# Mainsnode.net
KiCad netlist of a schematic drawn in EAGLE
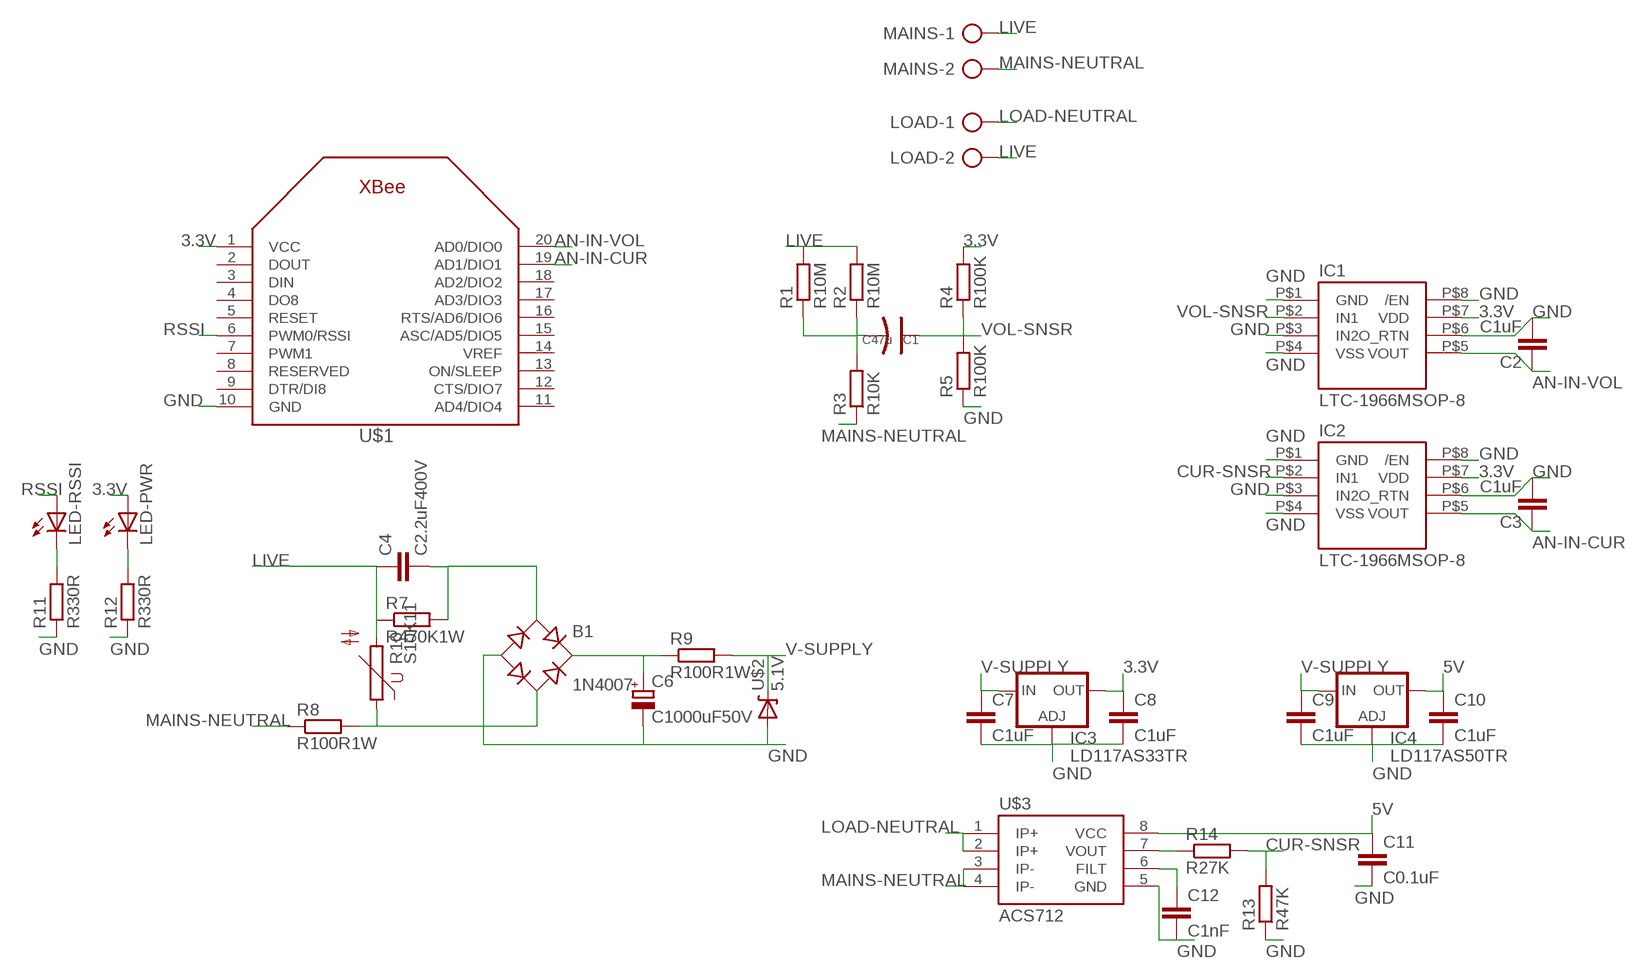
[diagram p0: schematic, sheet 1]

(export (version "E")
  (design (tool "Eeschema 10.0.6"))
  (components
    (comp (ref "B1")
      (value "1N4007")
      (footprint "eagle-import:RB1A")
      (libsource (lib "eagle-import") (part "RB1A"))
    )
    (comp (ref "C1")
      (value "C47u")
      (footprint "eagle-import:AVX-C")
      (libsource (lib "eagle-import") (part "C-POLAR-C"))
    )
    (comp (ref "C2")
      (value "C1uF")
      (footprint "eagle-import:C0805")
      (libsource (lib "eagle-import") (part "C-EUC0805"))
    )
    (comp (ref "C3")
      (value "C1uF")
      (footprint "eagle-import:C0805")
      (libsource (lib "eagle-import") (part "C-EUC0805"))
    )
    (comp (ref "C4")
      (value "C2.2uF400V")
      (footprint "eagle-import:C150-064X183")
      (libsource (lib "eagle-import") (part "C-EU150-064X183"))
    )
    (comp (ref "C6")
      (value "C1000uF50V")
      (footprint "eagle-import:E2-5")
      (libsource (lib "eagle-import") (part "CPOL-EUE2-5"))
    )
    (comp (ref "C7")
      (value "C1uF")
      (footprint "eagle-import:C0805")
      (libsource (lib "eagle-import") (part "C-EUC0805"))
    )
    (comp (ref "C8")
      (value "C1uF")
      (footprint "eagle-import:C0805")
      (libsource (lib "eagle-import") (part "C-EUC0805"))
    )
    (comp (ref "C9")
      (value "C1uF")
      (footprint "eagle-import:C0805")
      (libsource (lib "eagle-import") (part "C-EUC0805"))
    )
    (comp (ref "C10")
      (value "C1uF")
      (footprint "eagle-import:C0805")
      (libsource (lib "eagle-import") (part "C-EUC0805"))
    )
    (comp (ref "C11")
      (value "C0.1uF")
      (footprint "eagle-import:C0805")
      (libsource (lib "eagle-import") (part "C-EUC0805"))
    )
    (comp (ref "C12")
      (value "C1nF")
      (footprint "eagle-import:C0805")
      (libsource (lib "eagle-import") (part "C-EUC0805"))
    )
    (comp (ref "IC1")
      (value "LTC-1966MSOP-8")
      (footprint "eagle-import:MSOP-8")
      (libsource (lib "eagle-import") (part "LTC-1966MSOP-8"))
    )
    (comp (ref "IC2")
      (value "LTC-1966MSOP-8")
      (footprint "eagle-import:MSOP-8")
      (libsource (lib "eagle-import") (part "LTC-1966MSOP-8"))
    )
    (comp (ref "IC3")
      (value "LD117AS33TR")
      (footprint "eagle-import:SOT223")
      (libsource (lib "eagle-import") (part "LD117A?S33TR"))
    )
    (comp (ref "IC4")
      (value "LD117AS50TR")
      (footprint "eagle-import:SOT223")
      (libsource (lib "eagle-import") (part "LD117A?S50TR"))
    )
    (comp (ref "LED-PWR")
      (value "LED0603")
      (footprint "eagle-import:LED-0603")
      (libsource (lib "eagle-import") (part "LED0603"))
    )
    (comp (ref "LED-RSSI")
      (value "LED0603")
      (footprint "eagle-import:LED-0603")
      (libsource (lib "eagle-import") (part "LED0603"))
    )
    (comp (ref "LOAD")
      (value "AK300/2")
      (footprint "eagle-import:AK300_2")
      (libsource (lib "eagle-import") (part "AK300/2"))
    )
    (comp (ref "MAINS")
      (value "AK300/2")
      (footprint "eagle-import:AK300_2")
      (libsource (lib "eagle-import") (part "AK300/2"))
    )
    (comp (ref "R1")
      (value "R10M")
      (footprint "eagle-import:0309V")
      (libsource (lib "eagle-import") (part "R-EU_0309/V"))
    )
    (comp (ref "R2")
      (value "R10M")
      (footprint "eagle-import:R0603")
      (libsource (lib "eagle-import") (part "R-EU_R0603"))
    )
    (comp (ref "R3")
      (value "R10K")
      (footprint "eagle-import:R0603")
      (libsource (lib "eagle-import") (part "R-EU_R0603"))
    )
    (comp (ref "R4")
      (value "R100K")
      (footprint "eagle-import:R0603")
      (libsource (lib "eagle-import") (part "R-EU_R0603"))
    )
    (comp (ref "R5")
      (value "R100K")
      (footprint "eagle-import:R0603")
      (libsource (lib "eagle-import") (part "R-EU_R0603"))
    )
    (comp (ref "R7")
      (value "R470K1W")
      (footprint "eagle-import:0309V")
      (libsource (lib "eagle-import") (part "R-EU_0309/V"))
    )
    (comp (ref "R8")
      (value "R100R1W")
      (footprint "eagle-import:0309V")
      (libsource (lib "eagle-import") (part "R-EU_0309/V"))
    )
    (comp (ref "R9")
      (value "R100R1W")
      (footprint "eagle-import:0309V")
      (libsource (lib "eagle-import") (part "R-EU_0309/V"))
    )
    (comp (ref "R10")
      (value "S10K11")
      (footprint "eagle-import:S10K11")
      (libsource (lib "eagle-import") (part "S10K11"))
    )
    (comp (ref "R11")
      (value "R330R")
      (footprint "eagle-import:R0603")
      (libsource (lib "eagle-import") (part "R-EU_R0603"))
    )
    (comp (ref "R12")
      (value "R330R")
      (footprint "eagle-import:R0603")
      (libsource (lib "eagle-import") (part "R-EU_R0603"))
    )
    (comp (ref "R13")
      (value "R47K")
      (footprint "eagle-import:R0603")
      (libsource (lib "eagle-import") (part "R-EU_R0603"))
    )
    (comp (ref "R14")
      (value "R27K")
      (footprint "eagle-import:R0603")
      (libsource (lib "eagle-import") (part "R-EU_R0603"))
    )
    (comp (ref "U$1")
      (value "XBEE")
      (footprint "eagle-import:XBEE")
      (libsource (lib "eagle-import") (part "XBEE"))
    )
    (comp (ref "U$2")
      (value "5.1V")
      (footprint "eagle-import:DIODE-ZENER")
      (libsource (lib "eagle-import") (part "DIODE-ZENERPTH"))
    )
    (comp (ref "U$3")
      (value "ACS712")
      (footprint "eagle-import:SO08")
      (libsource (lib "eagle-import") (part "ACS712"))
    )
  )
  (nets
    (net (code "1") (name "/3.3V") (class "Default")
      (node (ref "C8") (pin "1") (pinfunction "1_1") (pintype "passive"))
      (node (ref "IC1") (pin "P$7") (pinfunction "VDD_P$7") (pintype "bidirectional"))
      (node (ref "IC2") (pin "P$7") (pinfunction "VDD_P$7") (pintype "bidirectional"))
      (node (ref "IC3") (pin "4") (pinfunction "OUT_4") (pintype "passive"))
      (node (ref "LED-PWR") (pin "A") (pinfunction "A_A") (pintype "passive"))
      (node (ref "R4") (pin "2") (pinfunction "2_2") (pintype "passive"))
      (node (ref "U$1") (pin "1") (pinfunction "VCC_1") (pintype "power_in"))
    )
    (net (code "2") (name "/5V") (class "Default")
      (node (ref "C10") (pin "1") (pinfunction "1_1") (pintype "passive"))
      (node (ref "C11") (pin "1") (pinfunction "1_1") (pintype "passive"))
      (node (ref "IC4") (pin "4") (pinfunction "OUT_4") (pintype "passive"))
      (node (ref "U$3") (pin "8") (pinfunction "VCC_8") (pintype "bidirectional"))
    )
    (net (code "3") (name "/AN-IN-CUR") (class "Default")
      (node (ref "C3") (pin "1") (pinfunction "1_1") (pintype "passive"))
      (node (ref "IC2") (pin "P$5") (pinfunction "VOUT_P$5") (pintype "bidirectional"))
      (node (ref "U$1") (pin "19") (pinfunction "AD1/DIO1_19") (pintype "bidirectional"))
    )
    (net (code "4") (name "/AN-IN-VOL") (class "Default")
      (node (ref "C2") (pin "1") (pinfunction "1_1") (pintype "passive"))
      (node (ref "IC1") (pin "P$5") (pinfunction "VOUT_P$5") (pintype "bidirectional"))
      (node (ref "U$1") (pin "20") (pinfunction "AD0/DIO0_20") (pintype "bidirectional"))
    )
    (net (code "5") (name "/CUR-SNSR") (class "Default")
      (node (ref "IC2") (pin "P$2") (pinfunction "IN1_P$2") (pintype "bidirectional"))
      (node (ref "R13") (pin "2") (pinfunction "2_2") (pintype "passive"))
      (node (ref "R14") (pin "2") (pinfunction "2_2") (pintype "passive"))
    )
    (net (code "6") (name "/GND") (class "Default")
      (node (ref "B1") (pin "-") (pinfunction "-_-") (pintype "passive"))
      (node (ref "C10") (pin "2") (pinfunction "2_2") (pintype "passive"))
      (node (ref "C11") (pin "2") (pinfunction "2_2") (pintype "passive"))
      (node (ref "C12") (pin "2") (pinfunction "2_2") (pintype "passive"))
      (node (ref "C2") (pin "2") (pinfunction "2_2") (pintype "passive"))
      (node (ref "C3") (pin "2") (pinfunction "2_2") (pintype "passive"))
      (node (ref "C6") (pin "-") (pinfunction "-_-") (pintype "passive"))
      (node (ref "C7") (pin "2") (pinfunction "2_2") (pintype "passive"))
      (node (ref "C8") (pin "2") (pinfunction "2_2") (pintype "passive"))
      (node (ref "C9") (pin "2") (pinfunction "2_2") (pintype "passive"))
      (node (ref "IC1") (pin "P$1") (pinfunction "GND_P$1") (pintype "bidirectional"))
      (node (ref "IC1") (pin "P$3") (pinfunction "IN2_P$3") (pintype "bidirectional"))
      (node (ref "IC1") (pin "P$4") (pinfunction "VSS_P$4") (pintype "bidirectional"))
      (node (ref "IC1") (pin "P$6") (pinfunction "O_RTN_P$6") (pintype "bidirectional"))
      (node (ref "IC1") (pin "P$8") (pinfunction "/EN_P$8") (pintype "bidirectional"))
      (node (ref "IC2") (pin "P$1") (pinfunction "GND_P$1") (pintype "bidirectional"))
      (node (ref "IC2") (pin "P$3") (pinfunction "IN2_P$3") (pintype "bidirectional"))
      (node (ref "IC2") (pin "P$4") (pinfunction "VSS_P$4") (pintype "bidirectional"))
      (node (ref "IC2") (pin "P$6") (pinfunction "O_RTN_P$6") (pintype "bidirectional"))
      (node (ref "IC2") (pin "P$8") (pinfunction "/EN_P$8") (pintype "bidirectional"))
      (node (ref "IC3") (pin "1") (pinfunction "ADJ_1") (pintype "input"))
      (node (ref "IC4") (pin "1") (pinfunction "ADJ_1") (pintype "input"))
      (node (ref "R11") (pin "1") (pinfunction "1_1") (pintype "passive"))
      (node (ref "R12") (pin "1") (pinfunction "1_1") (pintype "passive"))
      (node (ref "R13") (pin "1") (pinfunction "1_1") (pintype "passive"))
      (node (ref "R5") (pin "1") (pinfunction "1_1") (pintype "passive"))
      (node (ref "U$1") (pin "10") (pinfunction "GND_10") (pintype "power_in"))
      (node (ref "U$2") (pin "P$2") (pinfunction "A_P$2") (pintype "passive"))
      (node (ref "U$3") (pin "5") (pinfunction "GND_5") (pintype "bidirectional"))
    )
    (net (code "7") (name "/LIVE") (class "Default")
      (node (ref "C4") (pin "1") (pinfunction "1_1") (pintype "passive"))
      (node (ref "LOAD") (pin "2") (pinfunction "KL_2") (pintype "passive"))
      (node (ref "MAINS") (pin "1") (pinfunction "KL_1") (pintype "passive"))
      (node (ref "R1") (pin "2") (pinfunction "2_2") (pintype "passive"))
      (node (ref "R10") (pin "2") (pinfunction "2_2") (pintype "passive"))
      (node (ref "R2") (pin "2") (pinfunction "2_2") (pintype "passive"))
      (node (ref "R7") (pin "1") (pinfunction "1_1") (pintype "passive"))
    )
    (net (code "8") (name "/LOAD-NEUTRAL") (class "Default")
      (node (ref "LOAD") (pin "1") (pinfunction "KL_1") (pintype "passive"))
      (node (ref "U$3") (pin "1") (pinfunction "IP+_1") (pintype "bidirectional"))
      (node (ref "U$3") (pin "2") (pinfunction "IP+_2") (pintype "bidirectional"))
    )
    (net (code "9") (name "/MAINS-NEUTRAL") (class "Default")
      (node (ref "MAINS") (pin "2") (pinfunction "KL_2") (pintype "passive"))
      (node (ref "R3") (pin "1") (pinfunction "1_1") (pintype "passive"))
      (node (ref "R8") (pin "1") (pinfunction "1_1") (pintype "passive"))
      (node (ref "U$3") (pin "3") (pinfunction "IP-_3") (pintype "bidirectional"))
      (node (ref "U$3") (pin "4") (pinfunction "IP-_4") (pintype "bidirectional"))
    )
    (net (code "10") (name "/RSSI") (class "Default")
      (node (ref "LED-RSSI") (pin "A") (pinfunction "A_A") (pintype "passive"))
      (node (ref "U$1") (pin "6") (pinfunction "PWM0/RSSI_6") (pintype "output"))
    )
    (net (code "11") (name "/V-SUPPLY") (class "Default")
      (node (ref "C7") (pin "1") (pinfunction "1_1") (pintype "passive"))
      (node (ref "C9") (pin "1") (pinfunction "1_1") (pintype "passive"))
      (node (ref "IC3") (pin "3") (pinfunction "IN_3") (pintype "input"))
      (node (ref "IC4") (pin "3") (pinfunction "IN_3") (pintype "input"))
      (node (ref "R9") (pin "2") (pinfunction "2_2") (pintype "passive"))
      (node (ref "U$2") (pin "P$1") (pinfunction "C_P$1") (pintype "passive"))
    )
    (net (code "12") (name "/VOL-SNSR") (class "Default")
      (node (ref "C1") (pin "+") (pinfunction "1_+") (pintype "bidirectional"))
      (node (ref "IC1") (pin "P$2") (pinfunction "IN1_P$2") (pintype "bidirectional"))
      (node (ref "R4") (pin "1") (pinfunction "1_1") (pintype "passive"))
      (node (ref "R5") (pin "2") (pinfunction "2_2") (pintype "passive"))
    )
    (net (code "13") (name "Net-(B1-Pad+)") (class "Default")
      (node (ref "B1") (pin "+") (pinfunction "+_+") (pintype "passive"))
      (node (ref "C6") (pin "+") (pinfunction "+_+") (pintype "passive"))
      (node (ref "R9") (pin "1") (pinfunction "1_1") (pintype "passive"))
    )
    (net (code "14") (name "Net-(B1-PadAC1)") (class "Default")
      (node (ref "B1") (pin "AC1") (pinfunction "AC1_AC1") (pintype "passive"))
      (node (ref "C4") (pin "2") (pinfunction "2_2") (pintype "passive"))
      (node (ref "R7") (pin "2") (pinfunction "2_2") (pintype "passive"))
    )
    (net (code "15") (name "Net-(B1-PadAC2)") (class "Default")
      (node (ref "B1") (pin "AC2") (pinfunction "AC2_AC2") (pintype "passive"))
      (node (ref "R10") (pin "1") (pinfunction "1_1") (pintype "passive"))
      (node (ref "R8") (pin "2") (pinfunction "2_2") (pintype "passive"))
    )
    (net (code "16") (name "Net-(C1-2)") (class "Default")
      (node (ref "C1") (pin "-") (pinfunction "2_-") (pintype "bidirectional"))
      (node (ref "R1") (pin "1") (pinfunction "1_1") (pintype "passive"))
      (node (ref "R2") (pin "1") (pinfunction "1_1") (pintype "passive"))
      (node (ref "R3") (pin "2") (pinfunction "2_2") (pintype "passive"))
    )
    (net (code "17") (name "Net-(LED-PWR-PadC)") (class "Default")
      (node (ref "LED-PWR") (pin "C") (pinfunction "C_C") (pintype "passive"))
      (node (ref "R12") (pin "2") (pinfunction "2_2") (pintype "passive"))
    )
    (net (code "18") (name "Net-(LED-RSSI-PadC)") (class "Default")
      (node (ref "LED-RSSI") (pin "C") (pinfunction "C_C") (pintype "passive"))
      (node (ref "R11") (pin "2") (pinfunction "2_2") (pintype "passive"))
    )
    (net (code "19") (name "Net-(U$3-FILT)") (class "Default")
      (node (ref "C12") (pin "1") (pinfunction "1_1") (pintype "passive"))
      (node (ref "U$3") (pin "6") (pinfunction "FILT_6") (pintype "bidirectional"))
    )
    (net (code "20") (name "Net-(U$3-VOUT)") (class "Default")
      (node (ref "R14") (pin "1") (pinfunction "1_1") (pintype "passive"))
      (node (ref "U$3") (pin "7") (pinfunction "VOUT_7") (pintype "bidirectional"))
    )
    (net (code "21") (name "unconnected-(U$1-AD2{slash}DIO2-Pad18)") (class "Default")
      (node (ref "U$1") (pin "18") (pinfunction "AD2/DIO2_18") (pintype "bidirectional"))
    )
    (net (code "22") (name "unconnected-(U$1-AD3{slash}DIO3-Pad17)") (class "Default")
      (node (ref "U$1") (pin "17") (pinfunction "AD3/DIO3_17") (pintype "bidirectional"))
    )
    (net (code "23") (name "unconnected-(U$1-AD4{slash}DIO4-Pad11)") (class "Default")
      (node (ref "U$1") (pin "11") (pinfunction "AD4/DIO4_11") (pintype "bidirectional"))
    )
    (net (code "24") (name "unconnected-(U$1-ASC{slash}AD5{slash}DIO5-Pad15)") (class "Default")
      (node (ref "U$1") (pin "15") (pinfunction "ASC/AD5/DIO5_15") (pintype "bidirectional"))
    )
    (net (code "25") (name "unconnected-(U$1-CTS{slash}DIO7-Pad12)") (class "Default")
      (node (ref "U$1") (pin "12") (pinfunction "CTS/DIO7_12") (pintype "bidirectional"))
    )
    (net (code "26") (name "unconnected-(U$1-DIN-Pad3)") (class "Default")
      (node (ref "U$1") (pin "3") (pinfunction "DIN_3") (pintype "input"))
    )
    (net (code "27") (name "unconnected-(U$1-DO8-Pad4)") (class "Default")
      (node (ref "U$1") (pin "4") (pinfunction "DO8_4") (pintype "output"))
    )
    (net (code "28") (name "unconnected-(U$1-DOUT-Pad2)") (class "Default")
      (node (ref "U$1") (pin "2") (pinfunction "DOUT_2") (pintype "output"))
    )
    (net (code "29") (name "unconnected-(U$1-DTR{slash}DI8-Pad9)") (class "Default")
      (node (ref "U$1") (pin "9") (pinfunction "DTR/DI8_9") (pintype "input"))
    )
    (net (code "30") (name "unconnected-(U$1-ON{slash}SLEEP-Pad13)") (class "Default")
      (node (ref "U$1") (pin "13") (pinfunction "ON/SLEEP_13") (pintype "output"))
    )
    (net (code "31") (name "unconnected-(U$1-PWM1-Pad7)") (class "Default")
      (node (ref "U$1") (pin "7") (pinfunction "PWM1_7") (pintype "output"))
    )
    (net (code "32") (name "unconnected-(U$1-RESERVED-Pad8)") (class "Default")
      (node (ref "U$1") (pin "8") (pinfunction "RESERVED_8") (pintype "no_connect"))
    )
    (net (code "33") (name "unconnected-(U$1-RESET-Pad5)") (class "Default")
      (node (ref "U$1") (pin "5") (pinfunction "RESET_5") (pintype "input"))
    )
    (net (code "34") (name "unconnected-(U$1-RTS{slash}AD6{slash}DIO6-Pad16)") (class "Default")
      (node (ref "U$1") (pin "16") (pinfunction "RTS/AD6/DIO6_16") (pintype "bidirectional"))
    )
    (net (code "35") (name "unconnected-(U$1-VREF-Pad14)") (class "Default")
      (node (ref "U$1") (pin "14") (pinfunction "VREF_14") (pintype "input"))
    )
  )
)
